# 301_Photodiode_Board_Rev_2.net
KiCad netlist of a schematic drawn in EAGLE
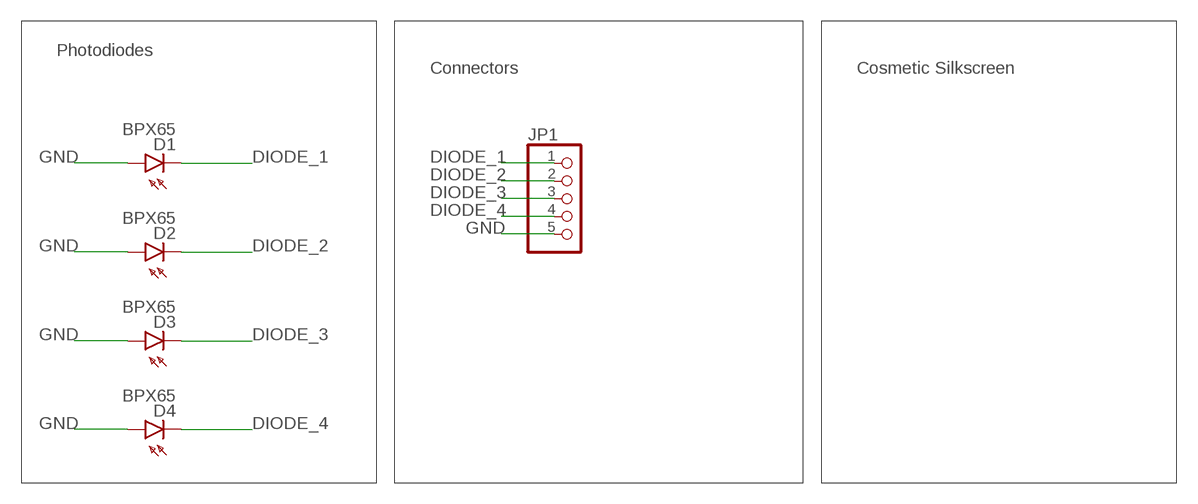
[diagram p0: schematic, sheet 1]

(export (version "E")
  (design (tool "Eeschema 10.0.6"))
  (components
    (comp (ref "D1")
      (value "BPX65")
      (footprint "eagle-import:BPX65")
      (fields (field (name "MPN") "BPX65."))
      (libsource (lib "eagle-import") (part "BPX65"))
    )
    (comp (ref "D2")
      (value "BPX65")
      (footprint "eagle-import:BPX65")
      (fields (field (name "MPN") "BPX65."))
      (libsource (lib "eagle-import") (part "BPX65"))
    )
    (comp (ref "D3")
      (value "BPX65")
      (footprint "eagle-import:BPX65")
      (fields (field (name "MPN") "BPX65."))
      (libsource (lib "eagle-import") (part "BPX65"))
    )
    (comp (ref "D4")
      (value "BPX65")
      (footprint "eagle-import:BPX65")
      (fields (field (name "MPN") "BPX65."))
      (libsource (lib "eagle-import") (part "BPX65"))
    )
    (comp (ref "JP1")
      (value "PINHD-1X5")
      (footprint "eagle-import:1X05")
      (libsource (lib "eagle-import") (part "PINHD-1X5"))
    )
  )
  (nets
    (net (code "1") (name "/DIODE_1") (class "Default")
      (node (ref "D1") (pin "K") (pinfunction "C_K") (pintype "passive"))
      (node (ref "JP1") (pin "1") (pinfunction "1_1") (pintype "passive"))
    )
    (net (code "2") (name "/DIODE_2") (class "Default")
      (node (ref "D2") (pin "K") (pinfunction "C_K") (pintype "passive"))
      (node (ref "JP1") (pin "2") (pinfunction "2_2") (pintype "passive"))
    )
    (net (code "3") (name "/DIODE_3") (class "Default")
      (node (ref "D3") (pin "K") (pinfunction "C_K") (pintype "passive"))
      (node (ref "JP1") (pin "3") (pinfunction "3_3") (pintype "passive"))
    )
    (net (code "4") (name "/DIODE_4") (class "Default")
      (node (ref "D4") (pin "K") (pinfunction "C_K") (pintype "passive"))
      (node (ref "JP1") (pin "4") (pinfunction "4_4") (pintype "passive"))
    )
    (net (code "5") (name "/GND") (class "Default")
      (node (ref "D1") (pin "A") (pinfunction "A_A") (pintype "passive"))
      (node (ref "D2") (pin "A") (pinfunction "A_A") (pintype "passive"))
      (node (ref "D3") (pin "A") (pinfunction "A_A") (pintype "passive"))
      (node (ref "D4") (pin "A") (pinfunction "A_A") (pintype "passive"))
      (node (ref "JP1") (pin "5") (pinfunction "5_5") (pintype "passive"))
    )
  )
)
